# main.net
KiCad netlist of a schematic drawn in Altium Designer
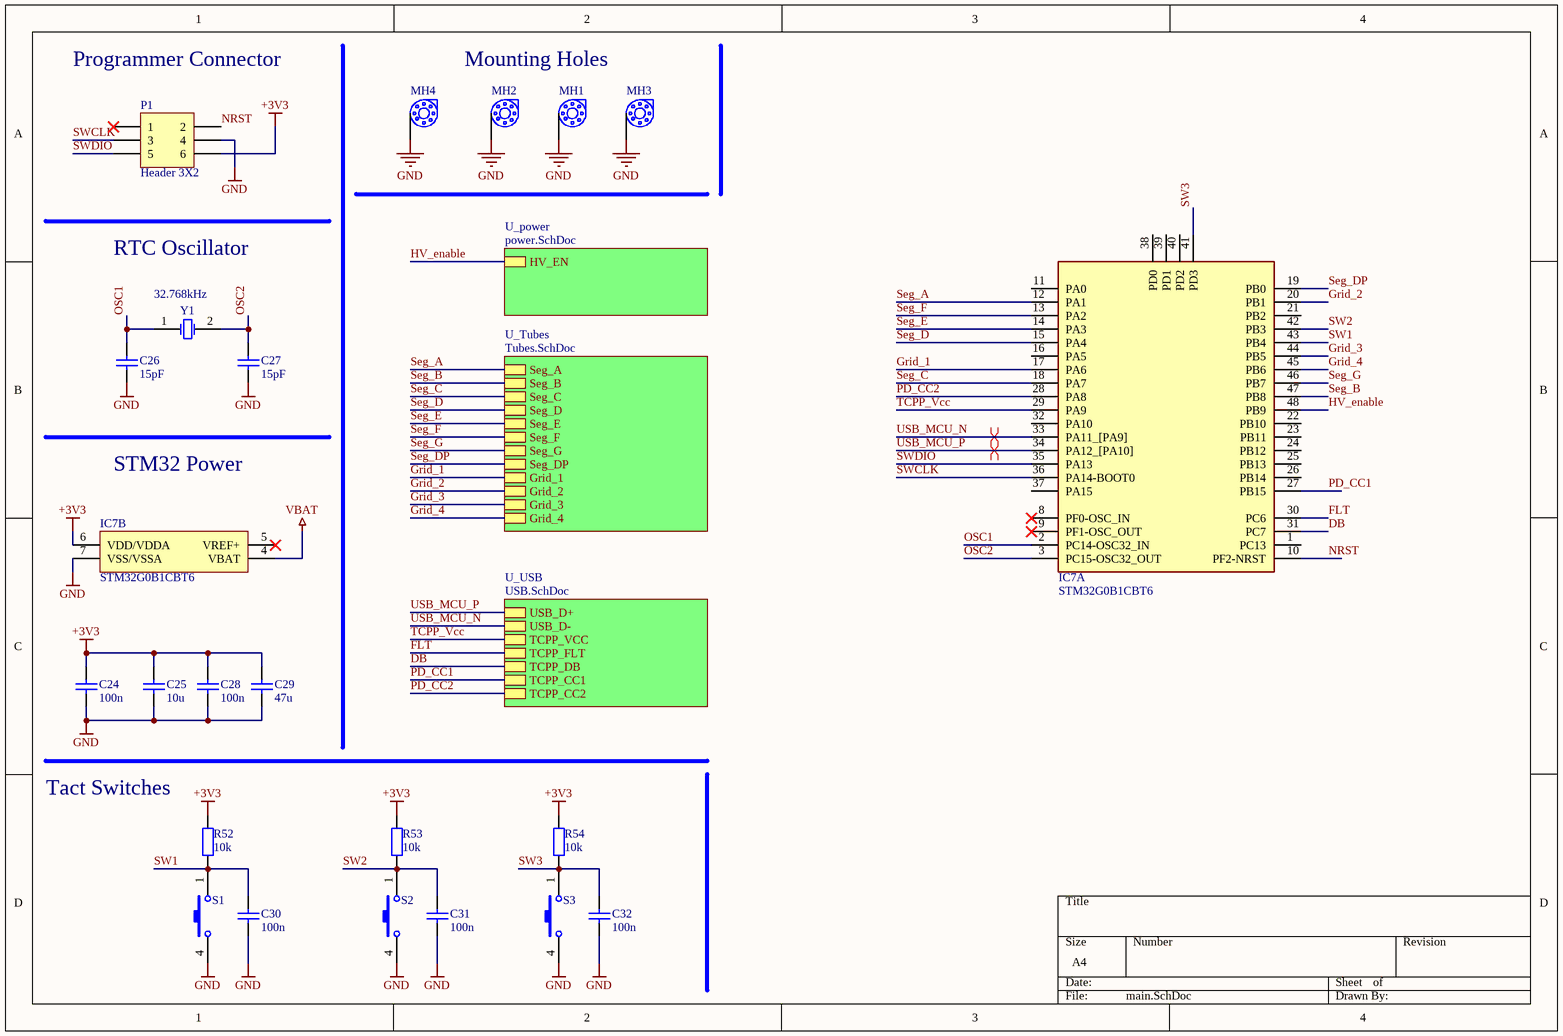
[diagram p0: main.SchDoc]

(export (version "E")
  (design (tool "Eeschema 10.0.6"))
  (components
    (comp (ref "C24")
      (value "100n")
      (footprint "Miscellaneous Devices:1608[0603]")
      (description "Capacitor")
      (fields (field (name "PUBLISHER") "Altium Limited"))
      (libsource (lib "Miscellaneous Devices") (part "Cap"))
    )
    (comp (ref "C25")
      (value "10u")
      (footprint "Miscellaneous Devices:1608[0603]")
      (description "Capacitor")
      (fields (field (name "PUBLISHER") "Altium Limited"))
      (libsource (lib "Miscellaneous Devices") (part "Cap"))
    )
    (comp (ref "C26")
      (value "15pF")
      (footprint "Miscellaneous Devices:1608[0603]")
      (description "Capacitor")
      (fields (field (name "PUBLISHER") "Altium Limited"))
      (libsource (lib "Miscellaneous Devices") (part "Cap"))
    )
    (comp (ref "C27")
      (value "15pF")
      (footprint "Miscellaneous Devices:1608[0603]")
      (description "Capacitor")
      (fields (field (name "PUBLISHER") "Altium Limited"))
      (libsource (lib "Miscellaneous Devices") (part "Cap"))
    )
    (comp (ref "C28")
      (value "100n")
      (footprint "Miscellaneous Devices:1608[0603]")
      (description "Capacitor")
      (fields (field (name "PUBLISHER") "Altium Limited"))
      (libsource (lib "Miscellaneous Devices") (part "Cap"))
    )
    (comp (ref "C29")
      (value "47u")
      (footprint "Miscellaneous Devices:1608[0603]")
      (description "Capacitor")
      (fields (field (name "PUBLISHER") "Altium Limited"))
      (libsource (lib "Miscellaneous Devices") (part "Cap"))
    )
    (comp (ref "C30")
      (value "100n")
      (footprint "Miscellaneous Devices:1608[0603]")
      (description "Capacitor")
      (fields (field (name "PUBLISHER") "Altium Limited"))
      (libsource (lib "Miscellaneous Devices") (part "Cap"))
    )
    (comp (ref "C31")
      (value "100n")
      (footprint "Miscellaneous Devices:1608[0603]")
      (description "Capacitor")
      (fields (field (name "PUBLISHER") "Altium Limited"))
      (libsource (lib "Miscellaneous Devices") (part "Cap"))
    )
    (comp (ref "C32")
      (value "100n")
      (footprint "Miscellaneous Devices:1608[0603]")
      (description "Capacitor")
      (fields (field (name "PUBLISHER") "Altium Limited"))
      (libsource (lib "Miscellaneous Devices") (part "Cap"))
    )
    (comp (ref "IC7")
      (value "STM32G0B1CBT6")
      (footprint "QFP50P900X900X160-48N")
      (description "Integrated Circuit")
      (fields (field (name "MOUSER PART NUMBER") "511-STM32G0B1CBT6"))
      (libsource (lib "Lib_VFD_Clock") (part "STM32G0B1CBT6"))
    )
    (comp (ref "MH1")
      (value "HOLE 2mm")
      (footprint "Lib_VFD_Clock:Hole")
      (libsource (lib "Lib_VFD_Clock") (part "MOUNT_HOLE_2MM_CORNER"))
    )
    (comp (ref "MH2")
      (value "HOLE 2mm")
      (footprint "Lib_VFD_Clock:Hole")
      (libsource (lib "Lib_VFD_Clock") (part "MOUNT_HOLE_2MM_CORNER"))
    )
    (comp (ref "MH3")
      (value "HOLE 2mm")
      (footprint "Lib_VFD_Clock:Hole")
      (libsource (lib "Lib_VFD_Clock") (part "MOUNT_HOLE_2MM_CORNER"))
    )
    (comp (ref "MH4")
      (value "HOLE 2mm")
      (footprint "Lib_VFD_Clock:Hole")
      (libsource (lib "Lib_VFD_Clock") (part "MOUNT_HOLE_2MM_CORNER"))
    )
    (comp (ref "P1")
      (value "Header 3X2")
      (footprint "HDR2X3")
      (description "Header, 3-Pin, Dual row")
      (fields (field (name "PUBLISHER") "Altium Limited"))
      (libsource (lib "Miscellaneous Connectors") (part "Header 3X2"))
    )
    (comp (ref "R52")
      (value "10k")
      (footprint "Miscellaneous Devices:J1-0603")
      (description "Resistor")
      (fields (field (name "PUBLISHER") "Altium Limited"))
      (libsource (lib "Miscellaneous Devices") (part "Res2"))
    )
    (comp (ref "R53")
      (value "10k")
      (footprint "Miscellaneous Devices:J1-0603")
      (description "Resistor")
      (fields (field (name "PUBLISHER") "Altium Limited"))
      (libsource (lib "Miscellaneous Devices") (part "Res2"))
    )
    (comp (ref "R54")
      (value "10k")
      (footprint "Miscellaneous Devices:J1-0603")
      (description "Resistor")
      (fields (field (name "PUBLISHER") "Altium Limited"))
      (libsource (lib "Miscellaneous Devices") (part "Res2"))
    )
    (comp (ref "S1")
      (value "PTS647SK70SMTR2N_LFS")
      (footprint "Lib_VFD_Clock:PTS647SK70SMTR2NLFS")
      (description "Switch (4-Pin Push)")
      (fields (field (name "MANUFACTURER_PART_NUMBER") "PTS647SK70SMTR2N LFS"))
      (libsource (lib "Lib_VFD_Clock") (part "PTS647SK70SMTR2N_LFS"))
    )
    (comp (ref "S2")
      (value "PTS647SK70SMTR2N_LFS")
      (footprint "Lib_VFD_Clock:PTS647SK70SMTR2NLFS")
      (description "Switch (4-Pin Push)")
      (fields (field (name "MANUFACTURER_PART_NUMBER") "PTS647SK70SMTR2N LFS"))
      (libsource (lib "Lib_VFD_Clock") (part "PTS647SK70SMTR2N_LFS"))
    )
    (comp (ref "S3")
      (value "PTS647SK70SMTR2N_LFS")
      (footprint "Lib_VFD_Clock:PTS647SK70SMTR2NLFS")
      (description "Switch (4-Pin Push)")
      (fields (field (name "MANUFACTURER_PART_NUMBER") "PTS647SK70SMTR2N LFS"))
      (libsource (lib "Lib_VFD_Clock") (part "PTS647SK70SMTR2N_LFS"))
    )
    (comp (ref "Y1")
      (value "32.768kHz")
      (footprint "ABS06N32768kHzT")
      (description "Crystal or Oscillator")
      (fields (field (name "MANUFACTURER_PART_NUMBER") "ABS06N-32.768kHz-T"))
      (libsource (lib "Lib_VFD_Clock") (part "ABS06N-32.768kHz-T"))
    )
  )
  (nets
    (net (code "1") (name "+3V3") (class "Default")
      (node (ref "C24") (pin "2") (pinfunction "2_2") (pintype "passive"))
      (node (ref "C25") (pin "2") (pinfunction "2_2") (pintype "passive"))
      (node (ref "C28") (pin "2") (pinfunction "2_2") (pintype "passive"))
      (node (ref "C29") (pin "2") (pinfunction "2_2") (pintype "passive"))
      (node (ref "IC7") (pin "6") (pinfunction "VDD/VDDA_6") (pintype "passive"))
      (node (ref "P1") (pin "6") (pinfunction "6_6") (pintype "passive"))
      (node (ref "R52") (pin "2") (pinfunction "2_2") (pintype "passive"))
      (node (ref "R53") (pin "2") (pinfunction "2_2") (pintype "passive"))
      (node (ref "R54") (pin "2") (pinfunction "2_2") (pintype "passive"))
    )
    (net (code "2") (name "/DB") (class "Default")
      (node (ref "IC7") (pin "31") (pinfunction "PC7_31") (pintype "passive"))
    )
    (net (code "3") (name "/FLT") (class "Default")
      (node (ref "IC7") (pin "30") (pinfunction "PC6_30") (pintype "passive"))
    )
    (net (code "4") (name "/Grid_1") (class "Default")
      (node (ref "IC7") (pin "17") (pinfunction "PA6_17") (pintype "passive"))
    )
    (net (code "5") (name "/Grid_2") (class "Default")
      (node (ref "IC7") (pin "20") (pinfunction "PB1_20") (pintype "passive"))
    )
    (net (code "6") (name "/Grid_3") (class "Default")
      (node (ref "IC7") (pin "44") (pinfunction "PB5_44") (pintype "passive"))
    )
    (net (code "7") (name "/Grid_4") (class "Default")
      (node (ref "IC7") (pin "45") (pinfunction "PB6_45") (pintype "passive"))
    )
    (net (code "8") (name "/HV_enable") (class "Default")
      (node (ref "IC7") (pin "48") (pinfunction "PB9_48") (pintype "passive"))
    )
    (net (code "9") (name "/NRST") (class "Default")
      (node (ref "IC7") (pin "10") (pinfunction "PF2-NRST_10") (pintype "passive"))
      (node (ref "P1") (pin "2") (pinfunction "2_2") (pintype "passive"))
    )
    (net (code "10") (name "/OSC1") (class "Default")
      (node (ref "C26") (pin "2") (pinfunction "2_2") (pintype "passive"))
      (node (ref "IC7") (pin "2") (pinfunction "PC14-OSC32_IN_2") (pintype "passive"))
      (node (ref "Y1") (pin "1") (pinfunction "1_1") (pintype "passive"))
    )
    (net (code "11") (name "/OSC2") (class "Default")
      (node (ref "C27") (pin "2") (pinfunction "2_2") (pintype "passive"))
      (node (ref "IC7") (pin "3") (pinfunction "PC15-OSC32_OUT_3") (pintype "passive"))
      (node (ref "Y1") (pin "2") (pinfunction "2_2") (pintype "passive"))
    )
    (net (code "12") (name "/PD_CC1") (class "Default")
      (node (ref "IC7") (pin "27") (pinfunction "PB15_27") (pintype "passive"))
    )
    (net (code "13") (name "/PD_CC2") (class "Default")
      (node (ref "IC7") (pin "28") (pinfunction "PA8_28") (pintype "passive"))
    )
    (net (code "14") (name "/SW1") (class "Default")
      (node (ref "C30") (pin "2") (pinfunction "2_2") (pintype "passive"))
      (node (ref "IC7") (pin "43") (pinfunction "PB4_43") (pintype "passive"))
      (node (ref "R52") (pin "1") (pinfunction "1_1") (pintype "passive"))
      (node (ref "S1") (pin "1") (pinfunction "NO_1_1") (pintype "passive"))
    )
    (net (code "15") (name "/SW2") (class "Default")
      (node (ref "C31") (pin "2") (pinfunction "2_2") (pintype "passive"))
      (node (ref "IC7") (pin "42") (pinfunction "PB3_42") (pintype "passive"))
      (node (ref "R53") (pin "1") (pinfunction "1_1") (pintype "passive"))
      (node (ref "S2") (pin "1") (pinfunction "NO_1_1") (pintype "passive"))
    )
    (net (code "16") (name "/SW3") (class "Default")
      (node (ref "C32") (pin "2") (pinfunction "2_2") (pintype "passive"))
      (node (ref "IC7") (pin "41") (pinfunction "PD3_41") (pintype "passive"))
      (node (ref "R54") (pin "1") (pinfunction "1_1") (pintype "passive"))
      (node (ref "S3") (pin "1") (pinfunction "NO_1_1") (pintype "passive"))
    )
    (net (code "17") (name "/SWCLK") (class "Default")
      (node (ref "IC7") (pin "36") (pinfunction "PA14-BOOT0_36") (pintype "passive"))
      (node (ref "P1") (pin "3") (pinfunction "3_3") (pintype "passive"))
    )
    (net (code "18") (name "/SWDIO") (class "Default")
      (node (ref "IC7") (pin "35") (pinfunction "PA13_35") (pintype "passive"))
      (node (ref "P1") (pin "5") (pinfunction "5_5") (pintype "passive"))
    )
    (net (code "19") (name "/Seg_A") (class "Default")
      (node (ref "IC7") (pin "12") (pinfunction "PA1_12") (pintype "passive"))
    )
    (net (code "20") (name "/Seg_B") (class "Default")
      (node (ref "IC7") (pin "47") (pinfunction "PB8_47") (pintype "passive"))
    )
    (net (code "21") (name "/Seg_C") (class "Default")
      (node (ref "IC7") (pin "18") (pinfunction "PA7_18") (pintype "passive"))
    )
    (net (code "22") (name "/Seg_D") (class "Default")
      (node (ref "IC7") (pin "15") (pinfunction "PA4_15") (pintype "passive"))
    )
    (net (code "23") (name "/Seg_DP") (class "Default")
      (node (ref "IC7") (pin "19") (pinfunction "PB0_19") (pintype "passive"))
    )
    (net (code "24") (name "/Seg_E") (class "Default")
      (node (ref "IC7") (pin "14") (pinfunction "PA3_14") (pintype "passive"))
    )
    (net (code "25") (name "/Seg_F") (class "Default")
      (node (ref "IC7") (pin "13") (pinfunction "PA2_13") (pintype "passive"))
    )
    (net (code "26") (name "/Seg_G") (class "Default")
      (node (ref "IC7") (pin "46") (pinfunction "PB7_46") (pintype "passive"))
    )
    (net (code "27") (name "/TCPP_Vcc") (class "Default")
      (node (ref "IC7") (pin "29") (pinfunction "PA9_29") (pintype "passive"))
    )
    (net (code "28") (name "/USB_MCU_N") (class "Default")
      (node (ref "IC7") (pin "33") (pinfunction "PA11_[PA9]_33") (pintype "passive"))
    )
    (net (code "29") (name "/USB_MCU_P") (class "Default")
      (node (ref "IC7") (pin "34") (pinfunction "PA12_[PA10]_34") (pintype "passive"))
    )
    (net (code "30") (name "GND") (class "Default")
      (node (ref "C24") (pin "1") (pinfunction "1_1") (pintype "passive"))
      (node (ref "C25") (pin "1") (pinfunction "1_1") (pintype "passive"))
      (node (ref "C26") (pin "1") (pinfunction "1_1") (pintype "passive"))
      (node (ref "C27") (pin "1") (pinfunction "1_1") (pintype "passive"))
      (node (ref "C28") (pin "1") (pinfunction "1_1") (pintype "passive"))
      (node (ref "C29") (pin "1") (pinfunction "1_1") (pintype "passive"))
      (node (ref "C30") (pin "1") (pinfunction "1_1") (pintype "passive"))
      (node (ref "C31") (pin "1") (pinfunction "1_1") (pintype "passive"))
      (node (ref "C32") (pin "1") (pinfunction "1_1") (pintype "passive"))
      (node (ref "IC7") (pin "7") (pinfunction "VSS/VSSA_7") (pintype "passive"))
      (node (ref "MH1") (pin "0") (pinfunction "GND_0") (pintype "passive"))
      (node (ref "MH2") (pin "0") (pinfunction "GND_0") (pintype "passive"))
      (node (ref "MH3") (pin "0") (pinfunction "GND_0") (pintype "passive"))
      (node (ref "MH4") (pin "0") (pinfunction "GND_0") (pintype "passive"))
      (node (ref "P1") (pin "4") (pinfunction "4_4") (pintype "passive"))
      (node (ref "S1") (pin "4") (pinfunction "COM_2_4") (pintype "passive"))
      (node (ref "S2") (pin "4") (pinfunction "COM_2_4") (pintype "passive"))
      (node (ref "S3") (pin "4") (pinfunction "COM_2_4") (pintype "passive"))
    )
    (net (code "31") (name "VBAT") (class "Default")
      (node (ref "IC7") (pin "4") (pinfunction "VBAT_4") (pintype "passive"))
    )
    (net (code "32") (name "unconnected-(IC7A-PA0-Pad11)") (class "Default")
      (node (ref "IC7") (pin "11") (pinfunction "PA0_11") (pintype "passive"))
    )
    (net (code "33") (name "unconnected-(IC7A-PA5-Pad16)") (class "Default")
      (node (ref "IC7") (pin "16") (pinfunction "PA5_16") (pintype "passive"))
    )
    (net (code "34") (name "unconnected-(IC7A-PA10-Pad32)") (class "Default")
      (node (ref "IC7") (pin "32") (pinfunction "PA10_32") (pintype "passive"))
    )
    (net (code "35") (name "unconnected-(IC7A-PA15-Pad37)") (class "Default")
      (node (ref "IC7") (pin "37") (pinfunction "PA15_37") (pintype "passive"))
    )
    (net (code "36") (name "unconnected-(IC7A-PB2-Pad21)") (class "Default")
      (node (ref "IC7") (pin "21") (pinfunction "PB2_21") (pintype "passive"))
    )
    (net (code "37") (name "unconnected-(IC7A-PB10-Pad22)") (class "Default")
      (node (ref "IC7") (pin "22") (pinfunction "PB10_22") (pintype "passive"))
    )
    (net (code "38") (name "unconnected-(IC7A-PB11-Pad23)") (class "Default")
      (node (ref "IC7") (pin "23") (pinfunction "PB11_23") (pintype "passive"))
    )
    (net (code "39") (name "unconnected-(IC7A-PB12-Pad24)") (class "Default")
      (node (ref "IC7") (pin "24") (pinfunction "PB12_24") (pintype "passive"))
    )
    (net (code "40") (name "unconnected-(IC7A-PB13-Pad25)") (class "Default")
      (node (ref "IC7") (pin "25") (pinfunction "PB13_25") (pintype "passive"))
    )
    (net (code "41") (name "unconnected-(IC7A-PB14-Pad26)") (class "Default")
      (node (ref "IC7") (pin "26") (pinfunction "PB14_26") (pintype "passive"))
    )
    (net (code "42") (name "unconnected-(IC7A-PC13-Pad1)") (class "Default")
      (node (ref "IC7") (pin "1") (pinfunction "PC13_1") (pintype "passive"))
    )
    (net (code "43") (name "unconnected-(IC7A-PD0-Pad38)") (class "Default")
      (node (ref "IC7") (pin "38") (pinfunction "PD0_38") (pintype "passive"))
    )
    (net (code "44") (name "unconnected-(IC7A-PD1-Pad39)") (class "Default")
      (node (ref "IC7") (pin "39") (pinfunction "PD1_39") (pintype "passive"))
    )
    (net (code "45") (name "unconnected-(IC7A-PD2-Pad40)") (class "Default")
      (node (ref "IC7") (pin "40") (pinfunction "PD2_40") (pintype "passive"))
    )
    (net (code "46") (name "unconnected-(IC7A-PF0-OSC_IN-Pad8)") (class "Default")
      (node (ref "IC7") (pin "8") (pinfunction "PF0-OSC_IN_8") (pintype "passive+no_connect"))
    )
    (net (code "47") (name "unconnected-(IC7A-PF1-OSC_OUT-Pad9)") (class "Default")
      (node (ref "IC7") (pin "9") (pinfunction "PF1-OSC_OUT_9") (pintype "passive+no_connect"))
    )
    (net (code "48") (name "unconnected-(IC7B-VREF+-Pad5)") (class "Default")
      (node (ref "IC7") (pin "5") (pinfunction "VREF+_5") (pintype "passive+no_connect"))
    )
    (net (code "49") (name "unconnected-(P1-Pad1)") (class "Default")
      (node (ref "P1") (pin "1") (pinfunction "1_1") (pintype "passive+no_connect"))
    )
  )
)
